# sensor.net
KiCad netlist of a schematic drawn in EAGLE
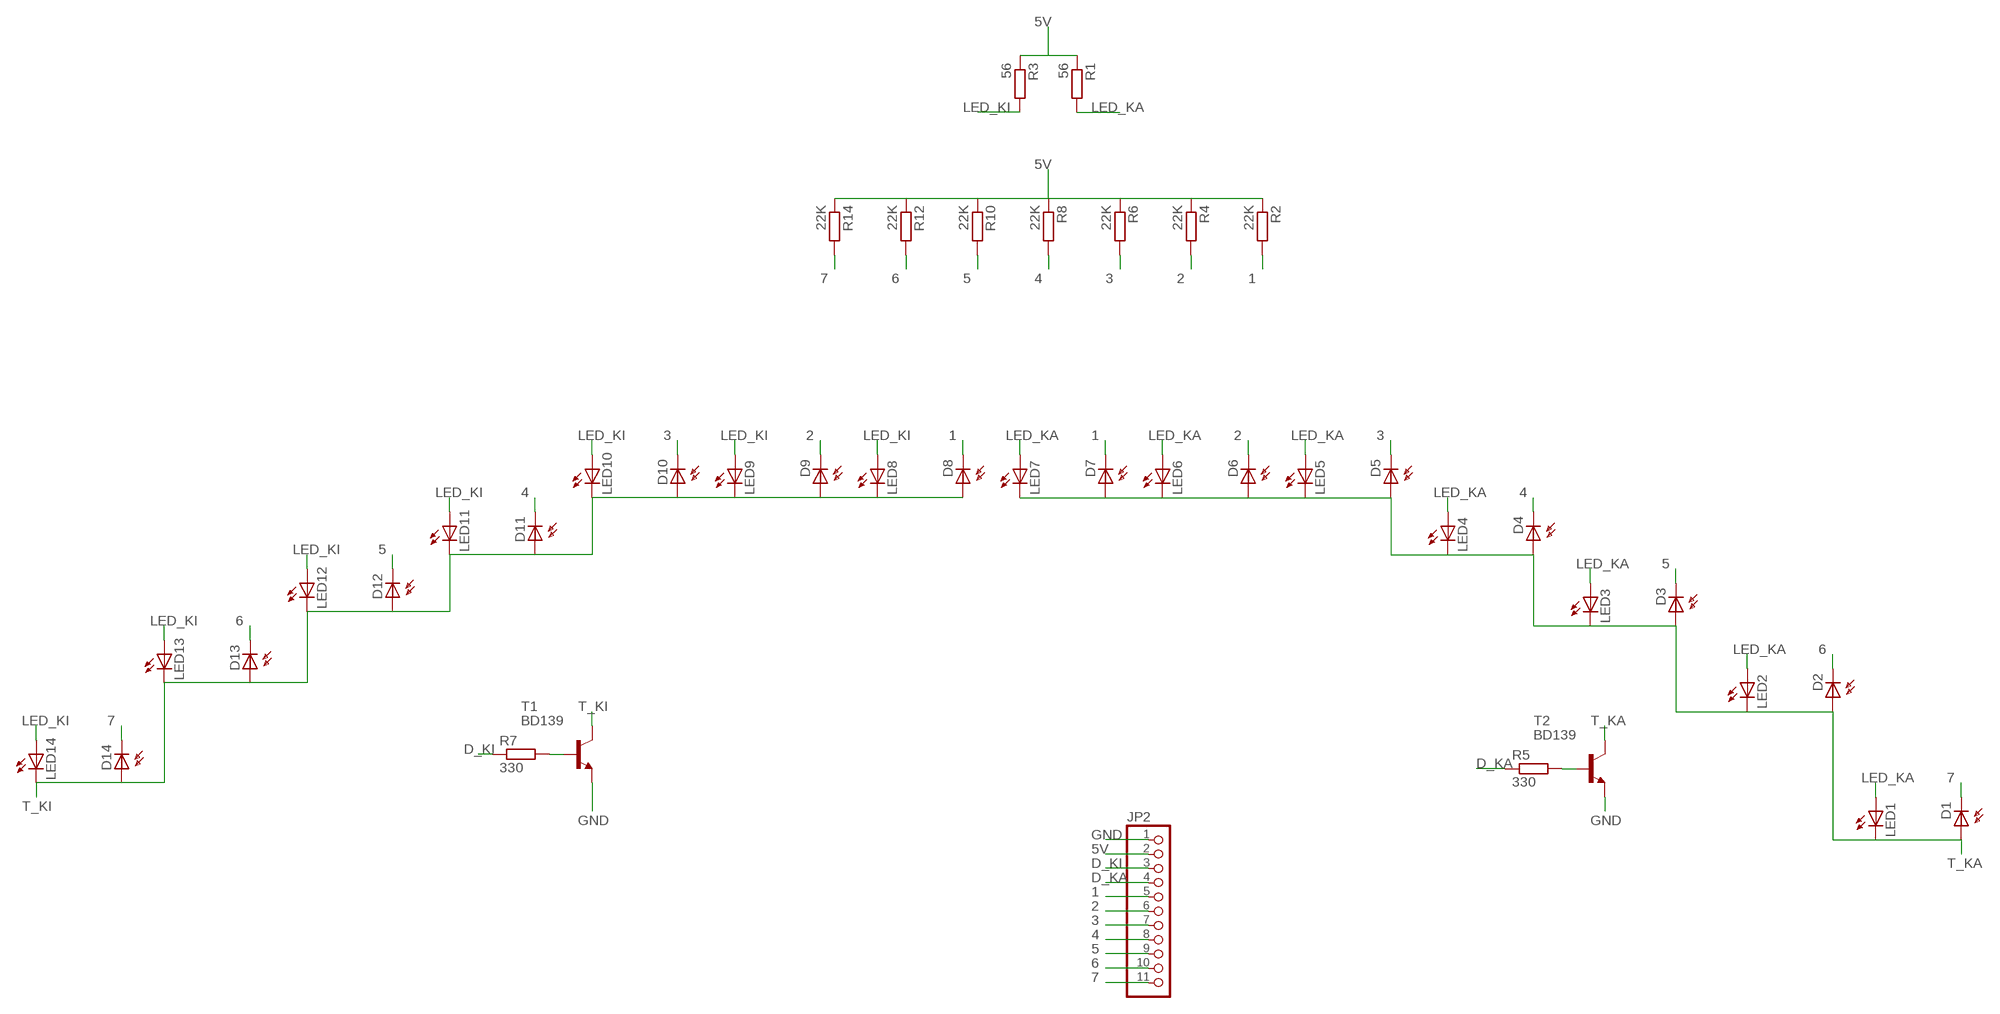
[diagram p0: schematic, sheet 1]

(export (version "E")
  (design (tool "Eeschema 10.0.6"))
  (components
    (comp (ref "D1")
      (value "BPX65")
      (footprint "eagle-import:BPX65")
      (fields (field (name "MPN") "BPX65."))
      (libsource (lib "eagle-import") (part "BPX65"))
    )
    (comp (ref "D2")
      (value "BPX65")
      (footprint "eagle-import:BPX65")
      (fields (field (name "MPN") "BPX65."))
      (libsource (lib "eagle-import") (part "BPX65"))
    )
    (comp (ref "D3")
      (value "BPX65")
      (footprint "eagle-import:BPX65")
      (fields (field (name "MPN") "BPX65."))
      (libsource (lib "eagle-import") (part "BPX65"))
    )
    (comp (ref "D4")
      (value "BPX65")
      (footprint "eagle-import:BPX65")
      (fields (field (name "MPN") "BPX65."))
      (libsource (lib "eagle-import") (part "BPX65"))
    )
    (comp (ref "D5")
      (value "BPX65")
      (footprint "eagle-import:BPX65")
      (fields (field (name "MPN") "BPX65."))
      (libsource (lib "eagle-import") (part "BPX65"))
    )
    (comp (ref "D6")
      (value "BPX65")
      (footprint "eagle-import:BPX65")
      (fields (field (name "MPN") "BPX65."))
      (libsource (lib "eagle-import") (part "BPX65"))
    )
    (comp (ref "D7")
      (value "BPX65")
      (footprint "eagle-import:BPX65")
      (fields (field (name "MPN") "BPX65."))
      (libsource (lib "eagle-import") (part "BPX65"))
    )
    (comp (ref "D8")
      (value "BPX65")
      (footprint "eagle-import:BPX65")
      (fields (field (name "MPN") "BPX65."))
      (libsource (lib "eagle-import") (part "BPX65"))
    )
    (comp (ref "D9")
      (value "BPX65")
      (footprint "eagle-import:BPX65")
      (fields (field (name "MPN") "BPX65."))
      (libsource (lib "eagle-import") (part "BPX65"))
    )
    (comp (ref "D10")
      (value "BPX65")
      (footprint "eagle-import:BPX65")
      (fields (field (name "MPN") "BPX65."))
      (libsource (lib "eagle-import") (part "BPX65"))
    )
    (comp (ref "D11")
      (value "BPX65")
      (footprint "eagle-import:BPX65")
      (fields (field (name "MPN") "BPX65."))
      (libsource (lib "eagle-import") (part "BPX65"))
    )
    (comp (ref "D12")
      (value "BPX65")
      (footprint "eagle-import:BPX65")
      (fields (field (name "MPN") "BPX65."))
      (libsource (lib "eagle-import") (part "BPX65"))
    )
    (comp (ref "D13")
      (value "BPX65")
      (footprint "eagle-import:BPX65")
      (fields (field (name "MPN") "BPX65."))
      (libsource (lib "eagle-import") (part "BPX65"))
    )
    (comp (ref "D14")
      (value "BPX65")
      (footprint "eagle-import:BPX65")
      (fields (field (name "MPN") "BPX65."))
      (libsource (lib "eagle-import") (part "BPX65"))
    )
    (comp (ref "JP2")
      (value "PINHD-1X11")
      (footprint "eagle-import:1X11")
      (libsource (lib "eagle-import") (part "PINHD-1X11"))
    )
    (comp (ref "LED1")
      (value "LED3MM")
      (footprint "eagle-import:LED3MM")
      (libsource (lib "eagle-import") (part "LED3MM"))
    )
    (comp (ref "LED2")
      (value "LED3MM")
      (footprint "eagle-import:LED3MM")
      (libsource (lib "eagle-import") (part "LED3MM"))
    )
    (comp (ref "LED3")
      (value "LED3MM")
      (footprint "eagle-import:LED3MM")
      (libsource (lib "eagle-import") (part "LED3MM"))
    )
    (comp (ref "LED4")
      (value "LED3MM")
      (footprint "eagle-import:LED3MM")
      (libsource (lib "eagle-import") (part "LED3MM"))
    )
    (comp (ref "LED5")
      (value "LED3MM")
      (footprint "eagle-import:LED3MM")
      (libsource (lib "eagle-import") (part "LED3MM"))
    )
    (comp (ref "LED6")
      (value "LED3MM")
      (footprint "eagle-import:LED3MM")
      (libsource (lib "eagle-import") (part "LED3MM"))
    )
    (comp (ref "LED7")
      (value "LED3MM")
      (footprint "eagle-import:LED3MM")
      (libsource (lib "eagle-import") (part "LED3MM"))
    )
    (comp (ref "LED8")
      (value "LED3MM")
      (footprint "eagle-import:LED3MM")
      (libsource (lib "eagle-import") (part "LED3MM"))
    )
    (comp (ref "LED9")
      (value "LED3MM")
      (footprint "eagle-import:LED3MM")
      (libsource (lib "eagle-import") (part "LED3MM"))
    )
    (comp (ref "LED10")
      (value "LED3MM")
      (footprint "eagle-import:LED3MM")
      (libsource (lib "eagle-import") (part "LED3MM"))
    )
    (comp (ref "LED11")
      (value "LED3MM")
      (footprint "eagle-import:LED3MM")
      (libsource (lib "eagle-import") (part "LED3MM"))
    )
    (comp (ref "LED12")
      (value "LED3MM")
      (footprint "eagle-import:LED3MM")
      (libsource (lib "eagle-import") (part "LED3MM"))
    )
    (comp (ref "LED13")
      (value "LED3MM")
      (footprint "eagle-import:LED3MM")
      (libsource (lib "eagle-import") (part "LED3MM"))
    )
    (comp (ref "LED14")
      (value "LED3MM")
      (footprint "eagle-import:LED3MM")
      (libsource (lib "eagle-import") (part "LED3MM"))
    )
    (comp (ref "R1")
      (value "56")
      (footprint "eagle-import:0207_7")
      (libsource (lib "eagle-import") (part "R-EU_0207/7"))
    )
    (comp (ref "R2")
      (value "22K")
      (footprint "eagle-import:0207_7")
      (libsource (lib "eagle-import") (part "R-EU_0207/7"))
    )
    (comp (ref "R3")
      (value "56")
      (footprint "eagle-import:0207_7")
      (libsource (lib "eagle-import") (part "R-EU_0207/7"))
    )
    (comp (ref "R4")
      (value "22K")
      (footprint "eagle-import:0207_7")
      (libsource (lib "eagle-import") (part "R-EU_0207/7"))
    )
    (comp (ref "R5")
      (value "330")
      (footprint "eagle-import:0207_7")
      (libsource (lib "eagle-import") (part "R-EU_0207/7"))
    )
    (comp (ref "R6")
      (value "22K")
      (footprint "eagle-import:0207_7")
      (libsource (lib "eagle-import") (part "R-EU_0207/7"))
    )
    (comp (ref "R7")
      (value "330")
      (footprint "eagle-import:0207_7")
      (libsource (lib "eagle-import") (part "R-EU_0207/7"))
    )
    (comp (ref "R8")
      (value "22K")
      (footprint "eagle-import:0207_7")
      (libsource (lib "eagle-import") (part "R-EU_0207/7"))
    )
    (comp (ref "R10")
      (value "22K")
      (footprint "eagle-import:0207_7")
      (libsource (lib "eagle-import") (part "R-EU_0207/7"))
    )
    (comp (ref "R12")
      (value "22K")
      (footprint "eagle-import:0207_7")
      (libsource (lib "eagle-import") (part "R-EU_0207/7"))
    )
    (comp (ref "R14")
      (value "22K")
      (footprint "eagle-import:0207_7")
      (libsource (lib "eagle-import") (part "R-EU_0207/7"))
    )
    (comp (ref "T1")
      (value "BD139")
      (footprint "eagle-import:TO126")
      (libsource (lib "eagle-import") (part "BD139"))
    )
    (comp (ref "T2")
      (value "BD139")
      (footprint "eagle-import:TO126")
      (libsource (lib "eagle-import") (part "BD139"))
    )
  )
  (nets
    (net (code "1") (name "/1") (class "Default")
      (node (ref "D7") (pin "K") (pinfunction "C_K") (pintype "passive"))
      (node (ref "D8") (pin "K") (pinfunction "C_K") (pintype "passive"))
      (node (ref "JP2") (pin "5") (pinfunction "5_5") (pintype "passive"))
      (node (ref "R2") (pin "2") (pinfunction "2_2") (pintype "passive"))
    )
    (net (code "2") (name "/2") (class "Default")
      (node (ref "D6") (pin "K") (pinfunction "C_K") (pintype "passive"))
      (node (ref "D9") (pin "K") (pinfunction "C_K") (pintype "passive"))
      (node (ref "JP2") (pin "6") (pinfunction "6_6") (pintype "passive"))
      (node (ref "R4") (pin "2") (pinfunction "2_2") (pintype "passive"))
    )
    (net (code "3") (name "/3") (class "Default")
      (node (ref "D10") (pin "K") (pinfunction "C_K") (pintype "passive"))
      (node (ref "D5") (pin "K") (pinfunction "C_K") (pintype "passive"))
      (node (ref "JP2") (pin "7") (pinfunction "7_7") (pintype "passive"))
      (node (ref "R6") (pin "2") (pinfunction "2_2") (pintype "passive"))
    )
    (net (code "4") (name "/4") (class "Default")
      (node (ref "D11") (pin "K") (pinfunction "C_K") (pintype "passive"))
      (node (ref "D4") (pin "K") (pinfunction "C_K") (pintype "passive"))
      (node (ref "JP2") (pin "8") (pinfunction "8_8") (pintype "passive"))
      (node (ref "R8") (pin "2") (pinfunction "2_2") (pintype "passive"))
    )
    (net (code "5") (name "/5") (class "Default")
      (node (ref "D12") (pin "K") (pinfunction "C_K") (pintype "passive"))
      (node (ref "D3") (pin "K") (pinfunction "C_K") (pintype "passive"))
      (node (ref "JP2") (pin "9") (pinfunction "9_9") (pintype "passive"))
      (node (ref "R10") (pin "2") (pinfunction "2_2") (pintype "passive"))
    )
    (net (code "6") (name "/5V") (class "Default")
      (node (ref "JP2") (pin "2") (pinfunction "2_2") (pintype "passive"))
      (node (ref "R1") (pin "1") (pinfunction "1_1") (pintype "passive"))
      (node (ref "R10") (pin "1") (pinfunction "1_1") (pintype "passive"))
      (node (ref "R12") (pin "1") (pinfunction "1_1") (pintype "passive"))
      (node (ref "R14") (pin "1") (pinfunction "1_1") (pintype "passive"))
      (node (ref "R2") (pin "1") (pinfunction "1_1") (pintype "passive"))
      (node (ref "R3") (pin "1") (pinfunction "1_1") (pintype "passive"))
      (node (ref "R4") (pin "1") (pinfunction "1_1") (pintype "passive"))
      (node (ref "R6") (pin "1") (pinfunction "1_1") (pintype "passive"))
      (node (ref "R8") (pin "1") (pinfunction "1_1") (pintype "passive"))
    )
    (net (code "7") (name "/6") (class "Default")
      (node (ref "D13") (pin "K") (pinfunction "C_K") (pintype "passive"))
      (node (ref "D2") (pin "K") (pinfunction "C_K") (pintype "passive"))
      (node (ref "JP2") (pin "10") (pinfunction "10_10") (pintype "passive"))
      (node (ref "R12") (pin "2") (pinfunction "2_2") (pintype "passive"))
    )
    (net (code "8") (name "/7") (class "Default")
      (node (ref "D1") (pin "K") (pinfunction "C_K") (pintype "passive"))
      (node (ref "D14") (pin "K") (pinfunction "C_K") (pintype "passive"))
      (node (ref "JP2") (pin "11") (pinfunction "11_11") (pintype "passive"))
      (node (ref "R14") (pin "2") (pinfunction "2_2") (pintype "passive"))
    )
    (net (code "9") (name "/D_KA") (class "Default")
      (node (ref "JP2") (pin "4") (pinfunction "4_4") (pintype "passive"))
      (node (ref "R5") (pin "1") (pinfunction "1_1") (pintype "passive"))
    )
    (net (code "10") (name "/D_KI") (class "Default")
      (node (ref "JP2") (pin "3") (pinfunction "3_3") (pintype "passive"))
      (node (ref "R7") (pin "1") (pinfunction "1_1") (pintype "passive"))
    )
    (net (code "11") (name "/GND") (class "Default")
      (node (ref "JP2") (pin "1") (pinfunction "1_1") (pintype "passive"))
      (node (ref "T1") (pin "1") (pinfunction "E_1") (pintype "passive"))
      (node (ref "T2") (pin "1") (pinfunction "E_1") (pintype "passive"))
    )
    (net (code "12") (name "/LED_KA") (class "Default")
      (node (ref "LED1") (pin "A") (pinfunction "A_A") (pintype "passive"))
      (node (ref "LED2") (pin "A") (pinfunction "A_A") (pintype "passive"))
      (node (ref "LED3") (pin "A") (pinfunction "A_A") (pintype "passive"))
      (node (ref "LED4") (pin "A") (pinfunction "A_A") (pintype "passive"))
      (node (ref "LED5") (pin "A") (pinfunction "A_A") (pintype "passive"))
      (node (ref "LED6") (pin "A") (pinfunction "A_A") (pintype "passive"))
      (node (ref "LED7") (pin "A") (pinfunction "A_A") (pintype "passive"))
      (node (ref "R1") (pin "2") (pinfunction "2_2") (pintype "passive"))
    )
    (net (code "13") (name "/LED_KI") (class "Default")
      (node (ref "LED10") (pin "A") (pinfunction "A_A") (pintype "passive"))
      (node (ref "LED11") (pin "A") (pinfunction "A_A") (pintype "passive"))
      (node (ref "LED12") (pin "A") (pinfunction "A_A") (pintype "passive"))
      (node (ref "LED13") (pin "A") (pinfunction "A_A") (pintype "passive"))
      (node (ref "LED14") (pin "A") (pinfunction "A_A") (pintype "passive"))
      (node (ref "LED8") (pin "A") (pinfunction "A_A") (pintype "passive"))
      (node (ref "LED9") (pin "A") (pinfunction "A_A") (pintype "passive"))
      (node (ref "R3") (pin "2") (pinfunction "2_2") (pintype "passive"))
    )
    (net (code "14") (name "/T_KA") (class "Default")
      (node (ref "D1") (pin "A") (pinfunction "A_A") (pintype "passive"))
      (node (ref "D2") (pin "A") (pinfunction "A_A") (pintype "passive"))
      (node (ref "D3") (pin "A") (pinfunction "A_A") (pintype "passive"))
      (node (ref "D4") (pin "A") (pinfunction "A_A") (pintype "passive"))
      (node (ref "D5") (pin "A") (pinfunction "A_A") (pintype "passive"))
      (node (ref "D6") (pin "A") (pinfunction "A_A") (pintype "passive"))
      (node (ref "D7") (pin "A") (pinfunction "A_A") (pintype "passive"))
      (node (ref "LED1") (pin "K") (pinfunction "C_K") (pintype "passive"))
      (node (ref "LED2") (pin "K") (pinfunction "C_K") (pintype "passive"))
      (node (ref "LED3") (pin "K") (pinfunction "C_K") (pintype "passive"))
      (node (ref "LED4") (pin "K") (pinfunction "C_K") (pintype "passive"))
      (node (ref "LED5") (pin "K") (pinfunction "C_K") (pintype "passive"))
      (node (ref "LED6") (pin "K") (pinfunction "C_K") (pintype "passive"))
      (node (ref "LED7") (pin "K") (pinfunction "C_K") (pintype "passive"))
      (node (ref "T2") (pin "2") (pinfunction "C_2") (pintype "passive"))
    )
    (net (code "15") (name "/T_KI") (class "Default")
      (node (ref "D10") (pin "A") (pinfunction "A_A") (pintype "passive"))
      (node (ref "D11") (pin "A") (pinfunction "A_A") (pintype "passive"))
      (node (ref "D12") (pin "A") (pinfunction "A_A") (pintype "passive"))
      (node (ref "D13") (pin "A") (pinfunction "A_A") (pintype "passive"))
      (node (ref "D14") (pin "A") (pinfunction "A_A") (pintype "passive"))
      (node (ref "D8") (pin "A") (pinfunction "A_A") (pintype "passive"))
      (node (ref "D9") (pin "A") (pinfunction "A_A") (pintype "passive"))
      (node (ref "LED10") (pin "K") (pinfunction "C_K") (pintype "passive"))
      (node (ref "LED11") (pin "K") (pinfunction "C_K") (pintype "passive"))
      (node (ref "LED12") (pin "K") (pinfunction "C_K") (pintype "passive"))
      (node (ref "LED13") (pin "K") (pinfunction "C_K") (pintype "passive"))
      (node (ref "LED14") (pin "K") (pinfunction "C_K") (pintype "passive"))
      (node (ref "LED8") (pin "K") (pinfunction "C_K") (pintype "passive"))
      (node (ref "LED9") (pin "K") (pinfunction "C_K") (pintype "passive"))
      (node (ref "T1") (pin "2") (pinfunction "C_2") (pintype "passive"))
    )
    (net (code "16") (name "Net-(T1-B)") (class "Default")
      (node (ref "R7") (pin "2") (pinfunction "2_2") (pintype "passive"))
      (node (ref "T1") (pin "3") (pinfunction "B_3") (pintype "passive"))
    )
    (net (code "17") (name "Net-(T2-B)") (class "Default")
      (node (ref "R5") (pin "2") (pinfunction "2_2") (pintype "passive"))
      (node (ref "T2") (pin "3") (pinfunction "B_3") (pintype "passive"))
    )
  )
)
